# sensor_tag.net
KiCad netlist of a schematic drawn in EAGLE
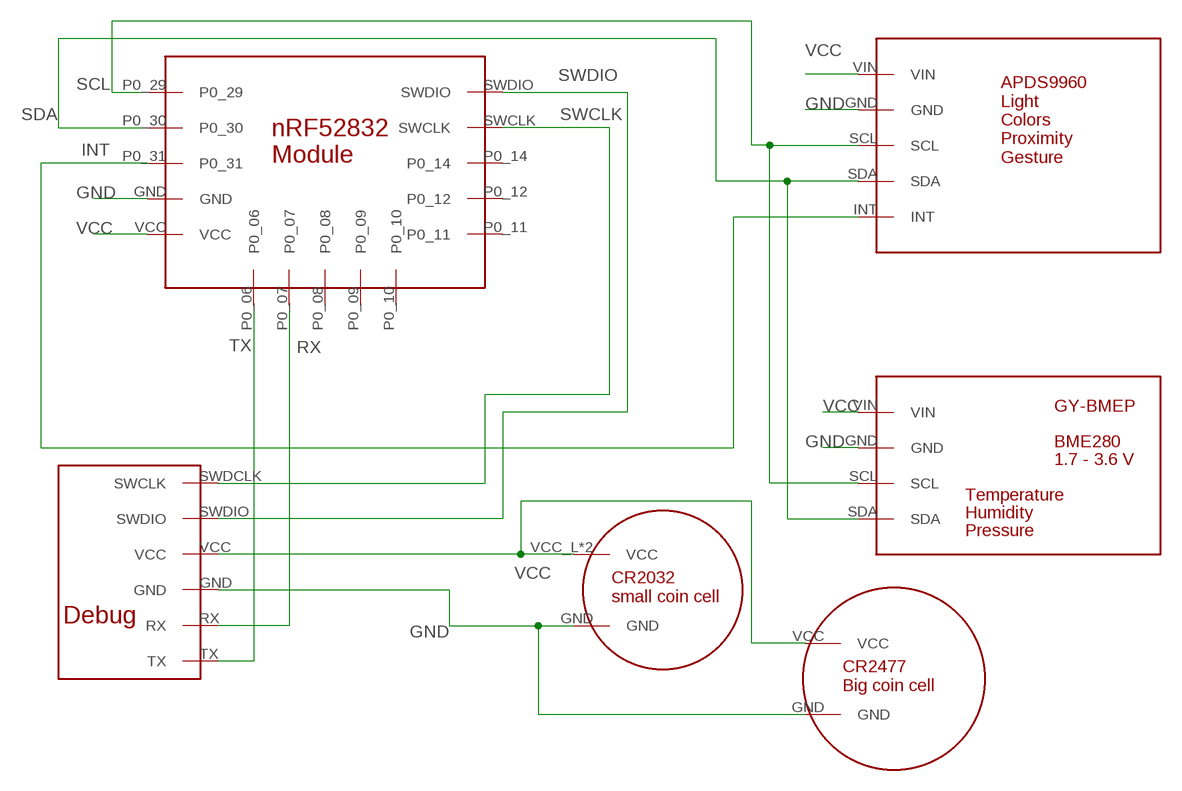
[diagram p0: schematic, sheet 1]

(export (version "E")
  (design (tool "Eeschema 10.0.6"))
  (components
    (comp (ref "U$1")
      (value "GY-BMEPGY-BMEP-NOHOLE")
      (footprint "eagle-import:GY-BMEP-NOHOLE")
      (libsource (lib "eagle-import") (part "GY-BMEPGY-BMEP-NOHOLE"))
    )
    (comp (ref "U$2")
      (value "APDS9960_MODULEAPDS9960-FULL")
      (footprint "eagle-import:APDS9960-FULL")
      (libsource (lib "eagle-import") (part "APDS9960_MODULEAPDS9960-FULL"))
    )
    (comp (ref "U$3")
      (value "NRF52832_MODULENRF52832_MOD_SMALL")
      (footprint "eagle-import:NRF52832_MOD_SMALL")
      (libsource (lib "eagle-import") (part "NRF52832_MODULENRF52832_MOD_SMALL"))
    )
    (comp (ref "U$4")
      (value "CR2032")
      (footprint "eagle-import:CR2032_SMD")
      (libsource (lib "eagle-import") (part "CR2032"))
    )
    (comp (ref "U$5")
      (value "NRF_TAG_DEBUG")
      (footprint "eagle-import:NRF_TAG_DEBUG")
      (libsource (lib "eagle-import") (part "NRF_TAG_DEBUG"))
    )
    (comp (ref "U$6")
      (value "CR2477")
      (footprint "eagle-import:CR2477")
      (libsource (lib "eagle-import") (part "CR2477"))
    )
  )
  (nets
    (net (code "1") (name "/GND") (class "Default")
      (node (ref "U$1") (pin "GND") (pinfunction "GND_GND") (pintype "bidirectional"))
      (node (ref "U$2") (pin "GND") (pinfunction "GND_GND") (pintype "bidirectional"))
      (node (ref "U$3") (pin "GND") (pinfunction "GND_GND") (pintype "bidirectional"))
      (node (ref "U$4") (pin "GND") (pinfunction "GND_GND") (pintype "bidirectional"))
      (node (ref "U$5") (pin "GND") (pinfunction "GND_GND") (pintype "bidirectional"))
      (node (ref "U$6") (pin "GND") (pinfunction "GND_GND") (pintype "bidirectional"))
    )
    (net (code "2") (name "/INT") (class "Default")
      (node (ref "U$2") (pin "INT") (pinfunction "INT_INT") (pintype "bidirectional"))
      (node (ref "U$3") (pin "P0_31") (pinfunction "P0_31_P0_31") (pintype "bidirectional"))
    )
    (net (code "3") (name "/RX") (class "Default")
      (node (ref "U$3") (pin "P0_07") (pinfunction "P0_07_P0_07") (pintype "bidirectional"))
      (node (ref "U$5") (pin "RX") (pinfunction "RX_RX") (pintype "bidirectional"))
    )
    (net (code "4") (name "/SCL") (class "Default")
      (node (ref "U$1") (pin "SCL") (pinfunction "SCL_SCL") (pintype "bidirectional"))
      (node (ref "U$2") (pin "SCL") (pinfunction "SCL_SCL") (pintype "bidirectional"))
      (node (ref "U$3") (pin "P0_29") (pinfunction "P0_29_P0_29") (pintype "bidirectional"))
    )
    (net (code "5") (name "/SDA") (class "Default")
      (node (ref "U$1") (pin "SDA") (pinfunction "SDA_SDA") (pintype "bidirectional"))
      (node (ref "U$2") (pin "SDA") (pinfunction "SDA_SDA") (pintype "bidirectional"))
      (node (ref "U$3") (pin "P0_30") (pinfunction "P0_30_P0_30") (pintype "bidirectional"))
    )
    (net (code "6") (name "/SWCLK") (class "Default")
      (node (ref "U$3") (pin "SWCLK") (pinfunction "SWCLK_SWCLK") (pintype "bidirectional"))
      (node (ref "U$5") (pin "SWDCLK") (pinfunction "SWCLK_SWDCLK") (pintype "bidirectional"))
    )
    (net (code "7") (name "/SWDIO") (class "Default")
      (node (ref "U$3") (pin "SWDIO") (pinfunction "SWDIO_SWDIO") (pintype "bidirectional"))
      (node (ref "U$5") (pin "SWDIO") (pinfunction "SWDIO_SWDIO") (pintype "bidirectional"))
    )
    (net (code "8") (name "/TX") (class "Default")
      (node (ref "U$3") (pin "P0_06") (pinfunction "P0_06_P0_06") (pintype "bidirectional"))
      (node (ref "U$5") (pin "TX") (pinfunction "TX_TX") (pintype "bidirectional"))
    )
    (net (code "9") (name "/VCC") (class "Default")
      (node (ref "U$1") (pin "VIN") (pinfunction "VIN_VIN") (pintype "bidirectional"))
      (node (ref "U$2") (pin "VIN") (pinfunction "VIN_VIN") (pintype "bidirectional"))
      (node (ref "U$3") (pin "VCC") (pinfunction "VCC_VCC") (pintype "bidirectional"))
      (node (ref "U$4") (pin "VCC_L") (pinfunction "VCC_VCC_L") (pintype "bidirectional"))
      (node (ref "U$4") (pin "VCC_R") (pinfunction "VCC_VCC_R") (pintype "bidirectional"))
      (node (ref "U$5") (pin "VCC") (pinfunction "VCC_VCC") (pintype "bidirectional"))
      (node (ref "U$6") (pin "VCC") (pinfunction "VCC_VCC") (pintype "bidirectional"))
    )
    (net (code "10") (name "unconnected-(U$3-PadP0_08)") (class "Default")
      (node (ref "U$3") (pin "P0_08") (pinfunction "P0_08_P0_08") (pintype "bidirectional"))
    )
    (net (code "11") (name "unconnected-(U$3-PadP0_09)") (class "Default")
      (node (ref "U$3") (pin "P0_09") (pinfunction "P0_09_P0_09") (pintype "bidirectional"))
    )
    (net (code "12") (name "unconnected-(U$3-PadP0_10)") (class "Default")
      (node (ref "U$3") (pin "P0_10") (pinfunction "P0_10_P0_10") (pintype "bidirectional"))
    )
    (net (code "13") (name "unconnected-(U$3-PadP0_11)") (class "Default")
      (node (ref "U$3") (pin "P0_11") (pinfunction "P0_11_P0_11") (pintype "bidirectional"))
    )
    (net (code "14") (name "unconnected-(U$3-PadP0_12)") (class "Default")
      (node (ref "U$3") (pin "P0_12") (pinfunction "P0_12_P0_12") (pintype "bidirectional"))
    )
    (net (code "15") (name "unconnected-(U$3-PadP0_14)") (class "Default")
      (node (ref "U$3") (pin "P0_14") (pinfunction "P0_14_P0_14") (pintype "bidirectional"))
    )
  )
)
